# mcu.net
KiCad netlist of a schematic drawn in Altium Designer
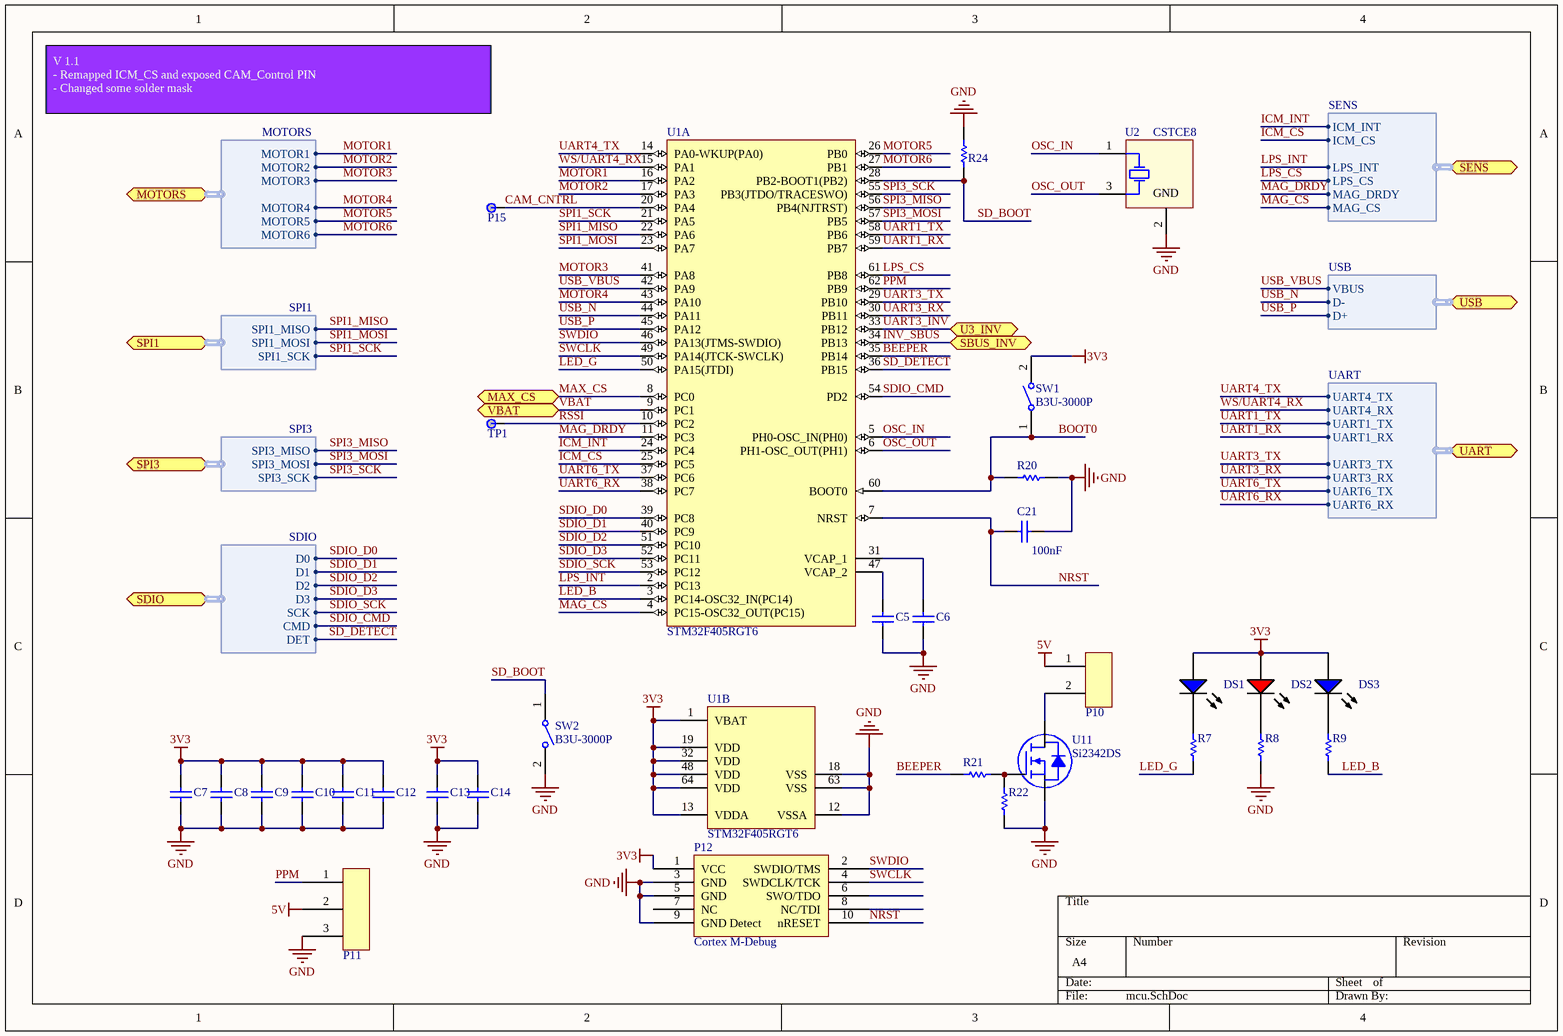
[diagram p0: mcu.SchDoc]

(export (version "E")
  (design (tool "Eeschema 10.0.6"))
  (components
    (comp (ref "C5")
      (value "CAP 2.2uF 6.3V 0603(1608)")
      (footprint "CAPC0603(1608)100_L")
      (description "CAP 2.2uF 6.3V ±10% 0603 (1608 Metric) Thickness 1mm SMD")
      (fields (field (name "TOLERANCE") "Â±10%"))
      (libsource (lib "Altium Content Vault") (part "CAP"))
    )
    (comp (ref "C6")
      (value "CAP 2.2uF 6.3V 0603(1608)")
      (footprint "CAPC0603(1608)100_L")
      (description "CAP 2.2uF 6.3V ±10% 0603 (1608 Metric) Thickness 1mm SMD")
      (fields (field (name "TOLERANCE") "Â±10%"))
      (libsource (lib "Altium Content Vault") (part "CAP"))
    )
    (comp (ref "C7")
      (value "CAP 100nF 35V 0402(1005)")
      (footprint "CAPC0402(1005)60_L")
      (description "CAP 100nF 35V ±10% 0402 (1005 Metric) Thickness 0.6mm SMD")
      (fields (field (name "TOLERANCE") "Â±10%"))
      (libsource (lib "Altium Content Vault") (part "CAP"))
    )
    (comp (ref "C8")
      (value "CAP 100nF 35V 0402(1005)")
      (footprint "CAPC0402(1005)60_L")
      (description "CAP 100nF 35V ±10% 0402 (1005 Metric) Thickness 0.6mm SMD")
      (fields (field (name "TOLERANCE") "Â±10%"))
      (libsource (lib "Altium Content Vault") (part "CAP"))
    )
    (comp (ref "C9")
      (value "CAP 100nF 35V 0402(1005)")
      (footprint "CAPC0402(1005)60_L")
      (description "CAP 100nF 35V ±10% 0402 (1005 Metric) Thickness 0.6mm SMD")
      (fields (field (name "TOLERANCE") "Â±10%"))
      (libsource (lib "Altium Content Vault") (part "CAP"))
    )
    (comp (ref "C10")
      (value "CAP 100nF 35V 0402(1005)")
      (footprint "CAPC0402(1005)60_L")
      (description "CAP 100nF 35V ±10% 0402 (1005 Metric) Thickness 0.6mm SMD")
      (fields (field (name "TOLERANCE") "Â±10%"))
      (libsource (lib "Altium Content Vault") (part "CAP"))
    )
    (comp (ref "C11")
      (value "CAP 100nF 35V 0402(1005)")
      (footprint "CAPC0402(1005)60_L")
      (description "CAP 100nF 35V ±10% 0402 (1005 Metric) Thickness 0.6mm SMD")
      (fields (field (name "TOLERANCE") "Â±10%"))
      (libsource (lib "Altium Content Vault") (part "CAP"))
    )
    (comp (ref "C12")
      (value "CAP 4.7uF 6.3V 0603(1608)")
      (footprint "CAPC0603(1608)100_M")
      (description "CAP 4.7uF 6.3V ±10% 0603 (1608 Metric) Thickness 1mm SMD")
      (fields (field (name "TOLERANCE") "Â±10%"))
      (libsource (lib "Altium Content Vault") (part "CAP"))
    )
    (comp (ref "C13")
      (value "CAP 1uF 6.3V 0603(1608)")
      (footprint "CAPC0603(1608)100_N")
      (description "CAP 1uF 6.3V ±10% 0603 (1608 Metric) Thickness 1mm SMD")
      (fields (field (name "TOLERANCE") "Â±10%"))
      (libsource (lib "Altium Content Vault") (part "CAP"))
    )
    (comp (ref "C14")
      (value "CAP 10nF 35V 0402(1005)")
      (footprint "CAPC0402(1005)60_M")
      (description "CAP 10nF 35V ±10% 0402 (1005 Metric) Thickness 0.6mm SMD")
      (fields (field (name "TOLERANCE") "Â±10%"))
      (libsource (lib "Altium Content Vault") (part "CAP"))
    )
    (comp (ref "C21")
      (value "100nF")
      (footprint "CAPC0402(1005)60_L")
      (description "CAP 100nF 35V ±10% 0402 (1005 Metric) Thickness 0.6mm SMD")
      (fields (field (name "TOLERANCE") "Â±10%") (field (name "Comment") "CAP 100nF 35V 0402(1005)"))
      (libsource (lib "Altium Content Vault") (part "CMP-1034-02075-1"))
    )
    (comp (ref "DS1")
      (value "TLMB1100-GS08")
      (footprint "VISH-TLMX1100-2_V")
      (description "Blue LED, 10 mA, 3.9 V, -40 to 100 degC, 2-Pin SMD (0603), RoHS, Tape and Reel")
      (fields (field (name "TOLERANCE") "10%"))
      (libsource (lib "Altium Content Vault") (part "CMP-1666-00028-1"))
    )
    (comp (ref "DS2")
      (value "TLMS1100-GS08")
      (footprint "VISH-TLMX1100_V")
      (description "LED, RED, 2.1 V, -40 to 100 degC, 2-Pin SMD (0603), RoHS, Tape and Reel")
      (fields (field (name "TOLERANCE") "5%"))
      (libsource (lib "Altium Content Vault") (part "CMP-1666-00027-1"))
    )
    (comp (ref "DS3")
      (value "TLMB1100-GS08")
      (footprint "VISH-TLMX1100-2_V")
      (description "Blue LED, 10 mA, 3.9 V, -40 to 100 degC, 2-Pin SMD (0603), RoHS, Tape and Reel")
      (fields (field (name "TOLERANCE") "10%"))
      (libsource (lib "Altium Content Vault") (part "CMP-1666-00028-1"))
    )
    (comp (ref "P10") (value "2 Pads") (footprint "other:2Pads") (libsource (lib "other") (part "2 Pads")))
    (comp (ref "P11") (value "3 Pads") (footprint "3Pads") (libsource (lib "MyLib") (part "3 Pads")))
    (comp (ref "P12")
      (value "Cortex M-Debug")
      (footprint "FTSH-105-01-XXX-DV-K")
      (description "Cortex M-Debug Connector")
      (libsource (lib "MyLib") (part "Cortex M Debug"))
    )
    (comp (ref "P15")
      (value "1Pads")
      (footprint "1PADS")
      (description "Pad")
      (libsource (lib "MyLib") (part "Test Point_1"))
    )
    (comp (ref "R7")
      (value "1K 5% 0402(1005)")
      (footprint "RESC0402(1005)_L")
      (description "1K 0.063W 5% 0402 (1005 Metric)  SMD")
      (fields (field (name "TOLERANCE") "5 %") (field (name "POWER") "0.063 W"))
      (libsource (lib "Altium Content Vault") (part "RES"))
    )
    (comp (ref "R8")
      (value "1K 5% 0402(1005)")
      (footprint "RESC0402(1005)_L")
      (description "1K 0.063W 5% 0402 (1005 Metric)  SMD")
      (fields (field (name "TOLERANCE") "5 %") (field (name "POWER") "0.063 W"))
      (libsource (lib "Altium Content Vault") (part "RES"))
    )
    (comp (ref "R9")
      (value "1K 5% 0402(1005)")
      (footprint "RESC0402(1005)_L")
      (description "1K 0.063W 5% 0402 (1005 Metric)  SMD")
      (fields (field (name "TOLERANCE") "5 %") (field (name "POWER") "0.063 W"))
      (libsource (lib "Altium Content Vault") (part "RES"))
    )
    (comp (ref "R20")
      (value "100K 5% 0402(1005)")
      (footprint "RESC0402(1005)_L")
      (description "100K 0.063W 5% 0402 (1005 Metric)  SMD")
      (fields (field (name "POWER") "0.063 W") (field (name "TOLERANCE") "5 %"))
      (libsource (lib "Altium Content Vault") (part "RES"))
    )
    (comp (ref "R21")
      (value "200R 5% 0402(1005)")
      (footprint "RESC0402(1005)_N")
      (description "200R 0.063W 5% 0402 (1005 Metric)  SMD")
      (fields (field (name "POWER") "0.063 W") (field (name "TOLERANCE") "5 %"))
      (libsource (lib "Altium Content Vault") (part "RES"))
    )
    (comp (ref "R22")
      (value "110K 5% 0402(1005)")
      (footprint "RESC0402(1005)_L")
      (description "110K 0.063W 5% 0402 (1005 Metric)  SMD")
      (fields (field (name "TOLERANCE") "5 %") (field (name "POWER") "0.063 W"))
      (libsource (lib "Altium Content Vault") (part "RES"))
    )
    (comp (ref "R24")
      (value "47K 5% 0402(1005)")
      (footprint "RESC0402(1005)_M")
      (description "47K 0.063W 5% 0402 (1005 Metric)  SMD")
      (fields (field (name "TOLERANCE") "5 %") (field (name "POWER") "0.063 W"))
      (libsource (lib "Altium Content Vault") (part "RES"))
    )
    (comp (ref "SW1")
      (value "B3U-3000P")
      (footprint "OMRON-B3U-3000P_V")
      (description "Ultra-Small Tactile Switch, 1 to 50 mA, 3 to 12 V, -25 to 70 degC, 2-Pin SMD, RoHS, Tape and Reel")
      (fields (field (name "TOLERANCE") "20%"))
      (libsource (lib "Altium Content Vault") (part "SW-SPST-2_B"))
    )
    (comp (ref "SW2")
      (value "B3U-3000P")
      (footprint "OMRON-B3U-3000P_V")
      (description "Ultra-Small Tactile Switch, 1 to 50 mA, 3 to 12 V, -25 to 70 degC, 2-Pin SMD, RoHS, Tape and Reel")
      (fields (field (name "TOLERANCE") "20%"))
      (libsource (lib "Altium Content Vault") (part "SW-SPST-2_B"))
    )
    (comp (ref "TP1") (value "Test Point") (footprint "TP") (libsource (lib "MyLib") (part "Test Point")))
    (comp (ref "U1")
      (value "STM32F405RGT6")
      (footprint "STM-LQFP64_M")
      (fields (field (name "MANUFACTURER") "STMicroelectronics"))
      (libsource (lib "Altium Content Vault") (part "MC-ARM-STM32F4X5-SQ64"))
    )
    (comp (ref "U2")
      (value "CSTCE8")
      (footprint "MURA-CSTCE_V-3_V")
      (fields (field (name "MANUFACTURER") "Murata"))
      (libsource (lib "Altium Content Vault") (part "CMP-0588-00001-2"))
    )
    (comp (ref "U11")
      (value "Si2342DS")
      (footprint "SOT23-3")
      (description "N Channel MOSFET")
      (libsource (lib "MyLib") (part "Si2342DS"))
    )
  )
  (nets
    (net (code "8") (name "/BEEPER") (class "Default")
      (node (ref "R21") (pin "1") (pinfunction "1_1") (pintype "passive"))
      (node (ref "U1") (pin "35") (pinfunction "PB14_35") (pintype "bidirectional"))
    )
    (net (code "9") (name "/BOOT0") (class "Default")
      (node (ref "R20") (pin "1") (pinfunction "1_1") (pintype "passive"))
      (node (ref "SW1") (pin "1") (pinfunction "1_1") (pintype "passive"))
      (node (ref "U1") (pin "60") (pinfunction "BOOT0_60") (pintype "input"))
    )
    (net (code "10") (name "/CAM_CNTRL") (class "Default")
      (node (ref "P15") (pin "1") (pinfunction "1_1") (pintype "passive"))
      (node (ref "U1") (pin "20") (pinfunction "PA4_20") (pintype "bidirectional"))
    )
    (net (code "11") (name "/ICM_CS") (class "Default")
      (node (ref "U1") (pin "25") (pinfunction "PC5_25") (pintype "bidirectional"))
    )
    (net (code "12") (name "/ICM_INT") (class "Default")
      (node (ref "U1") (pin "24") (pinfunction "PC4_24") (pintype "bidirectional"))
    )
    (net (code "13") (name "/INV_SBUS") (class "Default")
      (node (ref "U1") (pin "34") (pinfunction "PB13_34") (pintype "bidirectional"))
    )
    (net (code "14") (name "/LED_B") (class "Default")
      (node (ref "R9") (pin "1") (pinfunction "1_1") (pintype "passive"))
      (node (ref "U1") (pin "3") (pinfunction "PC14-OSC32_IN(PC14)_3") (pintype "bidirectional"))
    )
    (net (code "15") (name "/LED_G") (class "Default")
      (node (ref "R7") (pin "1") (pinfunction "1_1") (pintype "passive"))
      (node (ref "U1") (pin "50") (pinfunction "PA15(JTDI)_50") (pintype "bidirectional"))
    )
    (net (code "16") (name "/LPS_CS") (class "Default")
      (node (ref "U1") (pin "61") (pinfunction "PB8_61") (pintype "bidirectional"))
    )
    (net (code "17") (name "/LPS_INT") (class "Default")
      (node (ref "U1") (pin "2") (pinfunction "PC13_2") (pintype "bidirectional"))
    )
    (net (code "18") (name "/MAG_CS") (class "Default")
      (node (ref "U1") (pin "4") (pinfunction "PC15-OSC32_OUT(PC15)_4") (pintype "bidirectional"))
    )
    (net (code "19") (name "/MAG_DRDY") (class "Default")
      (node (ref "U1") (pin "11") (pinfunction "PC3_11") (pintype "bidirectional"))
    )
    (net (code "20") (name "/MAX_CS") (class "Default")
      (node (ref "U1") (pin "8") (pinfunction "PC0_8") (pintype "bidirectional"))
    )
    (net (code "21") (name "/MOTOR1") (class "Default")
      (node (ref "U1") (pin "16") (pinfunction "PA2_16") (pintype "bidirectional"))
    )
    (net (code "22") (name "/MOTOR2") (class "Default")
      (node (ref "U1") (pin "17") (pinfunction "PA3_17") (pintype "bidirectional"))
    )
    (net (code "23") (name "/MOTOR3") (class "Default")
      (node (ref "U1") (pin "41") (pinfunction "PA8_41") (pintype "bidirectional"))
    )
    (net (code "24") (name "/MOTOR4") (class "Default")
      (node (ref "U1") (pin "43") (pinfunction "PA10_43") (pintype "bidirectional"))
    )
    (net (code "25") (name "/MOTOR5") (class "Default")
      (node (ref "U1") (pin "26") (pinfunction "PB0_26") (pintype "bidirectional"))
    )
    (net (code "26") (name "/MOTOR6") (class "Default")
      (node (ref "U1") (pin "27") (pinfunction "PB1_27") (pintype "bidirectional"))
    )
    (net (code "27") (name "/NRST") (class "Default")
      (node (ref "C21") (pin "2") (pinfunction "2_2") (pintype "passive"))
      (node (ref "P12") (pin "10") (pinfunction "nRESET_10") (pintype "passive"))
      (node (ref "U1") (pin "7") (pinfunction "NRST_7") (pintype "bidirectional"))
    )
    (net (code "28") (name "/OSC_IN") (class "Default")
      (node (ref "U1") (pin "5") (pinfunction "PH0-OSC_IN(PH0)_5") (pintype "bidirectional"))
      (node (ref "U2") (pin "1") (pinfunction "C1_1") (pintype "passive"))
    )
    (net (code "29") (name "/OSC_OUT") (class "Default")
      (node (ref "U1") (pin "6") (pinfunction "PH1-OSC_OUT(PH1)_6") (pintype "bidirectional"))
      (node (ref "U2") (pin "3") (pinfunction "C2_3") (pintype "passive"))
    )
    (net (code "30") (name "/PPM") (class "Default")
      (node (ref "P11") (pin "1") (pinfunction "1_1") (pintype "passive"))
      (node (ref "U1") (pin "62") (pinfunction "PB9_62") (pintype "bidirectional"))
    )
    (net (code "31") (name "/RSSI") (class "Default")
      (node (ref "TP1") (pin "1") (pinfunction "1_1") (pintype "passive"))
      (node (ref "U1") (pin "10") (pinfunction "PC2_10") (pintype "bidirectional"))
    )
    (net (code "32") (name "/SDIO_CMD") (class "Default")
      (node (ref "U1") (pin "54") (pinfunction "PD2_54") (pintype "bidirectional"))
    )
    (net (code "33") (name "/SDIO_D0") (class "Default")
      (node (ref "U1") (pin "39") (pinfunction "PC8_39") (pintype "bidirectional"))
    )
    (net (code "34") (name "/SDIO_D1") (class "Default")
      (node (ref "U1") (pin "40") (pinfunction "PC9_40") (pintype "bidirectional"))
    )
    (net (code "35") (name "/SDIO_D2") (class "Default")
      (node (ref "U1") (pin "51") (pinfunction "PC10_51") (pintype "bidirectional"))
    )
    (net (code "36") (name "/SDIO_D3") (class "Default")
      (node (ref "U1") (pin "52") (pinfunction "PC11_52") (pintype "bidirectional"))
    )
    (net (code "37") (name "/SDIO_SCK") (class "Default")
      (node (ref "U1") (pin "53") (pinfunction "PC12_53") (pintype "bidirectional"))
    )
    (net (code "38") (name "/SD_BOOT") (class "Default")
      (node (ref "R24") (pin "1") (pinfunction "1_1") (pintype "passive"))
      (node (ref "SW2") (pin "1") (pinfunction "1_1") (pintype "passive"))
      (node (ref "U1") (pin "28") (pinfunction "PB2-BOOT1(PB2)_28") (pintype "bidirectional"))
    )
    (net (code "39") (name "/SD_DETECT") (class "Default")
      (node (ref "U1") (pin "36") (pinfunction "PB15_36") (pintype "bidirectional"))
    )
    (net (code "40") (name "/SPI1_MISO") (class "Default")
      (node (ref "U1") (pin "22") (pinfunction "PA6_22") (pintype "bidirectional"))
    )
    (net (code "41") (name "/SPI1_MOSI") (class "Default")
      (node (ref "U1") (pin "23") (pinfunction "PA7_23") (pintype "bidirectional"))
    )
    (net (code "42") (name "/SPI1_SCK") (class "Default")
      (node (ref "U1") (pin "21") (pinfunction "PA5_21") (pintype "bidirectional"))
    )
    (net (code "43") (name "/SPI3_MISO") (class "Default")
      (node (ref "U1") (pin "56") (pinfunction "PB4(NJTRST)_56") (pintype "bidirectional"))
    )
    (net (code "44") (name "/SPI3_MOSI") (class "Default")
      (node (ref "U1") (pin "57") (pinfunction "PB5_57") (pintype "bidirectional"))
    )
    (net (code "45") (name "/SPI3_SCK") (class "Default")
      (node (ref "U1") (pin "55") (pinfunction "PB3(JTDO/TRACESWO)_55") (pintype "bidirectional"))
    )
    (net (code "46") (name "/SWCLK") (class "Default")
      (node (ref "P12") (pin "4") (pinfunction "SWDCLK/TCK_4") (pintype "passive"))
      (node (ref "U1") (pin "49") (pinfunction "PA14(JTCK-SWCLK)_49") (pintype "bidirectional"))
    )
    (net (code "47") (name "/SWDIO") (class "Default")
      (node (ref "P12") (pin "2") (pinfunction "SWDIO/TMS_2") (pintype "passive"))
      (node (ref "U1") (pin "46") (pinfunction "PA13(JTMS-SWDIO)_46") (pintype "bidirectional"))
    )
    (net (code "48") (name "/UART1_RX") (class "Default")
      (node (ref "U1") (pin "59") (pinfunction "PB7_59") (pintype "bidirectional"))
    )
    (net (code "49") (name "/UART1_TX") (class "Default")
      (node (ref "U1") (pin "58") (pinfunction "PB6_58") (pintype "bidirectional"))
    )
    (net (code "50") (name "/UART3_INV") (class "Default")
      (node (ref "U1") (pin "33") (pinfunction "PB12_33") (pintype "bidirectional"))
    )
    (net (code "51") (name "/UART3_RX") (class "Default")
      (node (ref "U1") (pin "30") (pinfunction "PB11_30") (pintype "bidirectional"))
    )
    (net (code "52") (name "/UART3_TX") (class "Default")
      (node (ref "U1") (pin "29") (pinfunction "PB10_29") (pintype "bidirectional"))
    )
    (net (code "53") (name "/UART4_TX") (class "Default")
      (node (ref "U1") (pin "14") (pinfunction "PA0-WKUP(PA0)_14") (pintype "bidirectional"))
    )
    (net (code "54") (name "/UART6_RX") (class "Default")
      (node (ref "U1") (pin "38") (pinfunction "PC7_38") (pintype "bidirectional"))
    )
    (net (code "55") (name "/UART6_TX") (class "Default")
      (node (ref "U1") (pin "37") (pinfunction "PC6_37") (pintype "bidirectional"))
    )
    (net (code "56") (name "/USB_N") (class "Default")
      (node (ref "U1") (pin "44") (pinfunction "PA11_44") (pintype "bidirectional"))
    )
    (net (code "57") (name "/USB_P") (class "Default")
      (node (ref "U1") (pin "45") (pinfunction "PA12_45") (pintype "bidirectional"))
    )
    (net (code "58") (name "/USB_VBUS") (class "Default")
      (node (ref "U1") (pin "42") (pinfunction "PA9_42") (pintype "bidirectional"))
    )
    (net (code "59") (name "/VBAT") (class "Default")
      (node (ref "U1") (pin "9") (pinfunction "PC1_9") (pintype "bidirectional"))
    )
    (net (code "60") (name "/WS{slash}UART4_RX") (class "Default")
      (node (ref "U1") (pin "15") (pinfunction "PA1_15") (pintype "bidirectional"))
    )
    (net (code "68") (name "3V3") (class "Default")
      (node (ref "C10") (pin "2") (pinfunction "2_2") (pintype "passive"))
      (node (ref "C11") (pin "2") (pinfunction "2_2") (pintype "passive"))
      (node (ref "C12") (pin "2") (pinfunction "2_2") (pintype "passive"))
      (node (ref "C13") (pin "2") (pinfunction "2_2") (pintype "passive"))
      (node (ref "C14") (pin "2") (pinfunction "2_2") (pintype "passive"))
      (node (ref "C7") (pin "2") (pinfunction "2_2") (pintype "passive"))
      (node (ref "C8") (pin "2") (pinfunction "2_2") (pintype "passive"))
      (node (ref "C9") (pin "2") (pinfunction "2_2") (pintype "passive"))
      (node (ref "DS1") (pin "1") (pinfunction "A_1") (pintype "passive"))
      (node (ref "DS2") (pin "1") (pinfunction "A_1") (pintype "passive"))
      (node (ref "DS3") (pin "1") (pinfunction "A_1") (pintype "passive"))
      (node (ref "P12") (pin "1") (pinfunction "VCC_1") (pintype "passive"))
      (node (ref "SW1") (pin "2") (pinfunction "2_2") (pintype "passive"))
      (node (ref "U1") (pin "1") (pinfunction "VBAT_1") (pintype "power_in"))
      (node (ref "U1") (pin "13") (pinfunction "VDDA_13") (pintype "power_in"))
      (node (ref "U1") (pin "19") (pinfunction "VDD_19") (pintype "power_in"))
      (node (ref "U1") (pin "32") (pinfunction "VDD_32") (pintype "power_in"))
      (node (ref "U1") (pin "48") (pinfunction "VDD_48") (pintype "power_in"))
      (node (ref "U1") (pin "64") (pinfunction "VDD_64") (pintype "power_in"))
    )
    (net (code "69") (name "5V") (class "Default")
      (node (ref "P10") (pin "1") (pinfunction "1_1") (pintype "passive"))
      (node (ref "P11") (pin "2") (pinfunction "2_2") (pintype "passive"))
    )
    (net (code "70") (name "GND") (class "Default")
      (node (ref "C10") (pin "1") (pinfunction "1_1") (pintype "passive"))
      (node (ref "C11") (pin "1") (pinfunction "1_1") (pintype "passive"))
      (node (ref "C12") (pin "1") (pinfunction "1_1") (pintype "passive"))
      (node (ref "C13") (pin "1") (pinfunction "1_1") (pintype "passive"))
      (node (ref "C14") (pin "1") (pinfunction "1_1") (pintype "passive"))
      (node (ref "C21") (pin "1") (pinfunction "1_1") (pintype "passive"))
      (node (ref "C5") (pin "1") (pinfunction "1_1") (pintype "passive"))
      (node (ref "C6") (pin "1") (pinfunction "1_1") (pintype "passive"))
      (node (ref "C7") (pin "1") (pinfunction "1_1") (pintype "passive"))
      (node (ref "C8") (pin "1") (pinfunction "1_1") (pintype "passive"))
      (node (ref "C9") (pin "1") (pinfunction "1_1") (pintype "passive"))
      (node (ref "P11") (pin "3") (pinfunction "3_3") (pintype "passive"))
      (node (ref "P12") (pin "3") (pinfunction "GND_3") (pintype "passive"))
      (node (ref "P12") (pin "5") (pinfunction "GND_5") (pintype "passive"))
      (node (ref "P12") (pin "9") (pinfunction "GND_Detect_9") (pintype "passive"))
      (node (ref "R20") (pin "2") (pinfunction "2_2") (pintype "passive"))
      (node (ref "R22") (pin "1") (pinfunction "1_1") (pintype "passive"))
      (node (ref "R24") (pin "2") (pinfunction "2_2") (pintype "passive"))
      (node (ref "R8") (pin "1") (pinfunction "1_1") (pintype "passive"))
      (node (ref "SW2") (pin "2") (pinfunction "2_2") (pintype "passive"))
      (node (ref "U1") (pin "12") (pinfunction "VSSA_12") (pintype "power_in"))
      (node (ref "U1") (pin "18") (pinfunction "VSS_18") (pintype "power_in"))
      (node (ref "U1") (pin "63") (pinfunction "VSS_63") (pintype "power_in"))
      (node (ref "U11") (pin "2") (pinfunction "S_2") (pintype "passive"))
      (node (ref "U2") (pin "2") (pinfunction "GND_2") (pintype "power_in"))
    )
    (net (code "71") (name "Net-(DS1-K)") (class "Default")
      (node (ref "DS1") (pin "2") (pinfunction "K_2") (pintype "passive"))
      (node (ref "R7") (pin "2") (pinfunction "2_2") (pintype "passive"))
    )
    (net (code "72") (name "Net-(DS2-K)") (class "Default")
      (node (ref "DS2") (pin "2") (pinfunction "K_2") (pintype "passive"))
      (node (ref "R8") (pin "2") (pinfunction "2_2") (pintype "passive"))
    )
    (net (code "73") (name "Net-(DS3-K)") (class "Default")
      (node (ref "DS3") (pin "2") (pinfunction "K_2") (pintype "passive"))
      (node (ref "R9") (pin "2") (pinfunction "2_2") (pintype "passive"))
    )
    (net (code "74") (name "Net-(U1A-VCAP_1)") (class "Default")
      (node (ref "C6") (pin "2") (pinfunction "2_2") (pintype "passive"))
      (node (ref "U1") (pin "31") (pinfunction "VCAP_1_31") (pintype "power_in"))
    )
    (net (code "75") (name "Net-(U1A-VCAP_2)") (class "Default")
      (node (ref "C5") (pin "2") (pinfunction "2_2") (pintype "passive"))
      (node (ref "U1") (pin "47") (pinfunction "VCAP_2_47") (pintype "power_in"))
    )
    (net (code "76") (name "Net-(U11-D)") (class "Default")
      (node (ref "P10") (pin "2") (pinfunction "2_2") (pintype "passive"))
      (node (ref "U11") (pin "3") (pinfunction "D_3") (pintype "passive"))
    )
    (net (code "77") (name "Net-(U11-G)") (class "Default")
      (node (ref "R21") (pin "2") (pinfunction "2_2") (pintype "passive"))
      (node (ref "R22") (pin "2") (pinfunction "2_2") (pintype "passive"))
      (node (ref "U11") (pin "1") (pinfunction "G_1") (pintype "passive"))
    )
    (net (code "78") (name "unconnected-(P12-NC-Pad7)") (class "Default")
      (node (ref "P12") (pin "7") (pinfunction "NC_7") (pintype "passive"))
    )
    (net (code "79") (name "unconnected-(P12-NC{slash}TDI-Pad8)") (class "Default")
      (node (ref "P12") (pin "8") (pinfunction "NC/TDI_8") (pintype "passive"))
    )
    (net (code "80") (name "unconnected-(P12-SWO{slash}TDO-Pad6)") (class "Default")
      (node (ref "P12") (pin "6") (pinfunction "SWO/TDO_6") (pintype "passive"))
    )
  )
)
